# Botones.net
KiCad netlist of a schematic drawn in EAGLE
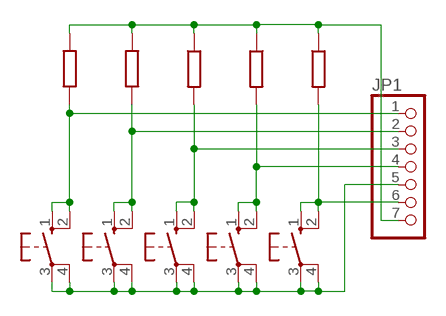
[diagram p0: schematic, sheet 1]

(export (version "E")
  (design (tool "Eeschema 10.0.6"))
  (components
    (comp (ref "ABAJO")
      (value "10-XX")
      (footprint "eagle-import:B3F-10XX")
      (fields (field (name "MPN") "B3F-1000"))
      (libsource (lib "eagle-import") (part "10-XX"))
    )
    (comp (ref "ARRIBA")
      (value "10-XX")
      (footprint "eagle-import:B3F-10XX")
      (fields (field (name "MPN") "B3F-1000"))
      (libsource (lib "eagle-import") (part "10-XX"))
    )
    (comp (ref "DERECHA")
      (value "10-XX")
      (footprint "eagle-import:B3F-10XX")
      (fields (field (name "MPN") "B3F-1000"))
      (libsource (lib "eagle-import") (part "10-XX"))
    )
    (comp (ref "IZQUIERDA")
      (value "10-XX")
      (footprint "eagle-import:B3F-10XX")
      (fields (field (name "MPN") "B3F-1000"))
      (libsource (lib "eagle-import") (part "10-XX"))
    )
    (comp (ref "JP1")
      (value "PINHD-1X7")
      (footprint "eagle-import:1X07")
      (libsource (lib "eagle-import") (part "PINHD-1X7"))
    )
    (comp (ref "MENU")
      (value "10-XX")
      (footprint "eagle-import:B3F-10XX")
      (fields (field (name "MPN") "B3F-1000"))
      (libsource (lib "eagle-import") (part "10-XX"))
    )
    (comp (ref "R14")
      (value "10K")
      (footprint "eagle-import:0204_7")
      (libsource (lib "eagle-import") (part "R-EU_0204/7"))
    )
    (comp (ref "R15")
      (value "10K")
      (footprint "eagle-import:0204_7")
      (libsource (lib "eagle-import") (part "R-EU_0204/7"))
    )
    (comp (ref "R34")
      (value "10K")
      (footprint "eagle-import:0204_7")
      (libsource (lib "eagle-import") (part "R-EU_0204/7"))
    )
    (comp (ref "R35")
      (value "10K")
      (footprint "eagle-import:0204_7")
      (libsource (lib "eagle-import") (part "R-EU_0204/7"))
    )
    (comp (ref "R36")
      (value "10K")
      (footprint "eagle-import:0204_7")
      (libsource (lib "eagle-import") (part "R-EU_0204/7"))
    )
  )
  (nets
    (net (code "1") (name "Net-(ABAJO-P)") (class "Default")
      (node (ref "ABAJO") (pin "3") (pinfunction "P_3") (pintype "passive"))
      (node (ref "ABAJO") (pin "4") (pinfunction "P1_4") (pintype "passive"))
      (node (ref "ARRIBA") (pin "3") (pinfunction "P_3") (pintype "passive"))
      (node (ref "ARRIBA") (pin "4") (pinfunction "P1_4") (pintype "passive"))
      (node (ref "DERECHA") (pin "3") (pinfunction "P_3") (pintype "passive"))
      (node (ref "DERECHA") (pin "4") (pinfunction "P1_4") (pintype "passive"))
      (node (ref "IZQUIERDA") (pin "3") (pinfunction "P_3") (pintype "passive"))
      (node (ref "IZQUIERDA") (pin "4") (pinfunction "P1_4") (pintype "passive"))
      (node (ref "JP1") (pin "5") (pinfunction "5_5") (pintype "passive"))
      (node (ref "MENU") (pin "3") (pinfunction "P_3") (pintype "passive"))
      (node (ref "MENU") (pin "4") (pinfunction "P1_4") (pintype "passive"))
    )
    (net (code "2") (name "Net-(ABAJO-S)") (class "Default")
      (node (ref "ABAJO") (pin "1") (pinfunction "S_1") (pintype "passive"))
      (node (ref "ABAJO") (pin "2") (pinfunction "S1_2") (pintype "passive"))
      (node (ref "JP1") (pin "2") (pinfunction "2_2") (pintype "passive"))
      (node (ref "R14") (pin "1") (pinfunction "1_1") (pintype "passive"))
    )
    (net (code "3") (name "Net-(ARRIBA-S)") (class "Default")
      (node (ref "ARRIBA") (pin "1") (pinfunction "S_1") (pintype "passive"))
      (node (ref "ARRIBA") (pin "2") (pinfunction "S1_2") (pintype "passive"))
      (node (ref "JP1") (pin "1") (pinfunction "1_1") (pintype "passive"))
      (node (ref "R15") (pin "1") (pinfunction "1_1") (pintype "passive"))
    )
    (net (code "4") (name "Net-(DERECHA-S)") (class "Default")
      (node (ref "DERECHA") (pin "1") (pinfunction "S_1") (pintype "passive"))
      (node (ref "DERECHA") (pin "2") (pinfunction "S1_2") (pintype "passive"))
      (node (ref "JP1") (pin "6") (pinfunction "6_6") (pintype "passive"))
      (node (ref "R36") (pin "2") (pinfunction "2_2") (pintype "passive"))
    )
    (net (code "5") (name "Net-(IZQUIERDA-S)") (class "Default")
      (node (ref "IZQUIERDA") (pin "1") (pinfunction "S_1") (pintype "passive"))
      (node (ref "IZQUIERDA") (pin "2") (pinfunction "S1_2") (pintype "passive"))
      (node (ref "JP1") (pin "4") (pinfunction "4_4") (pintype "passive"))
      (node (ref "R35") (pin "2") (pinfunction "2_2") (pintype "passive"))
    )
    (net (code "6") (name "Net-(JP1-Pad7)") (class "Default")
      (node (ref "JP1") (pin "7") (pinfunction "7_7") (pintype "passive"))
      (node (ref "R14") (pin "2") (pinfunction "2_2") (pintype "passive"))
      (node (ref "R15") (pin "2") (pinfunction "2_2") (pintype "passive"))
      (node (ref "R34") (pin "1") (pinfunction "1_1") (pintype "passive"))
      (node (ref "R35") (pin "1") (pinfunction "1_1") (pintype "passive"))
      (node (ref "R36") (pin "1") (pinfunction "1_1") (pintype "passive"))
    )
    (net (code "7") (name "Net-(MENU-S)") (class "Default")
      (node (ref "JP1") (pin "3") (pinfunction "3_3") (pintype "passive"))
      (node (ref "MENU") (pin "1") (pinfunction "S_1") (pintype "passive"))
      (node (ref "MENU") (pin "2") (pinfunction "S1_2") (pintype "passive"))
      (node (ref "R34") (pin "2") (pinfunction "2_2") (pintype "passive"))
    )
  )
)
